# FPGA_Banks_GTH.net
KiCad netlist of a schematic drawn in Altium Designer
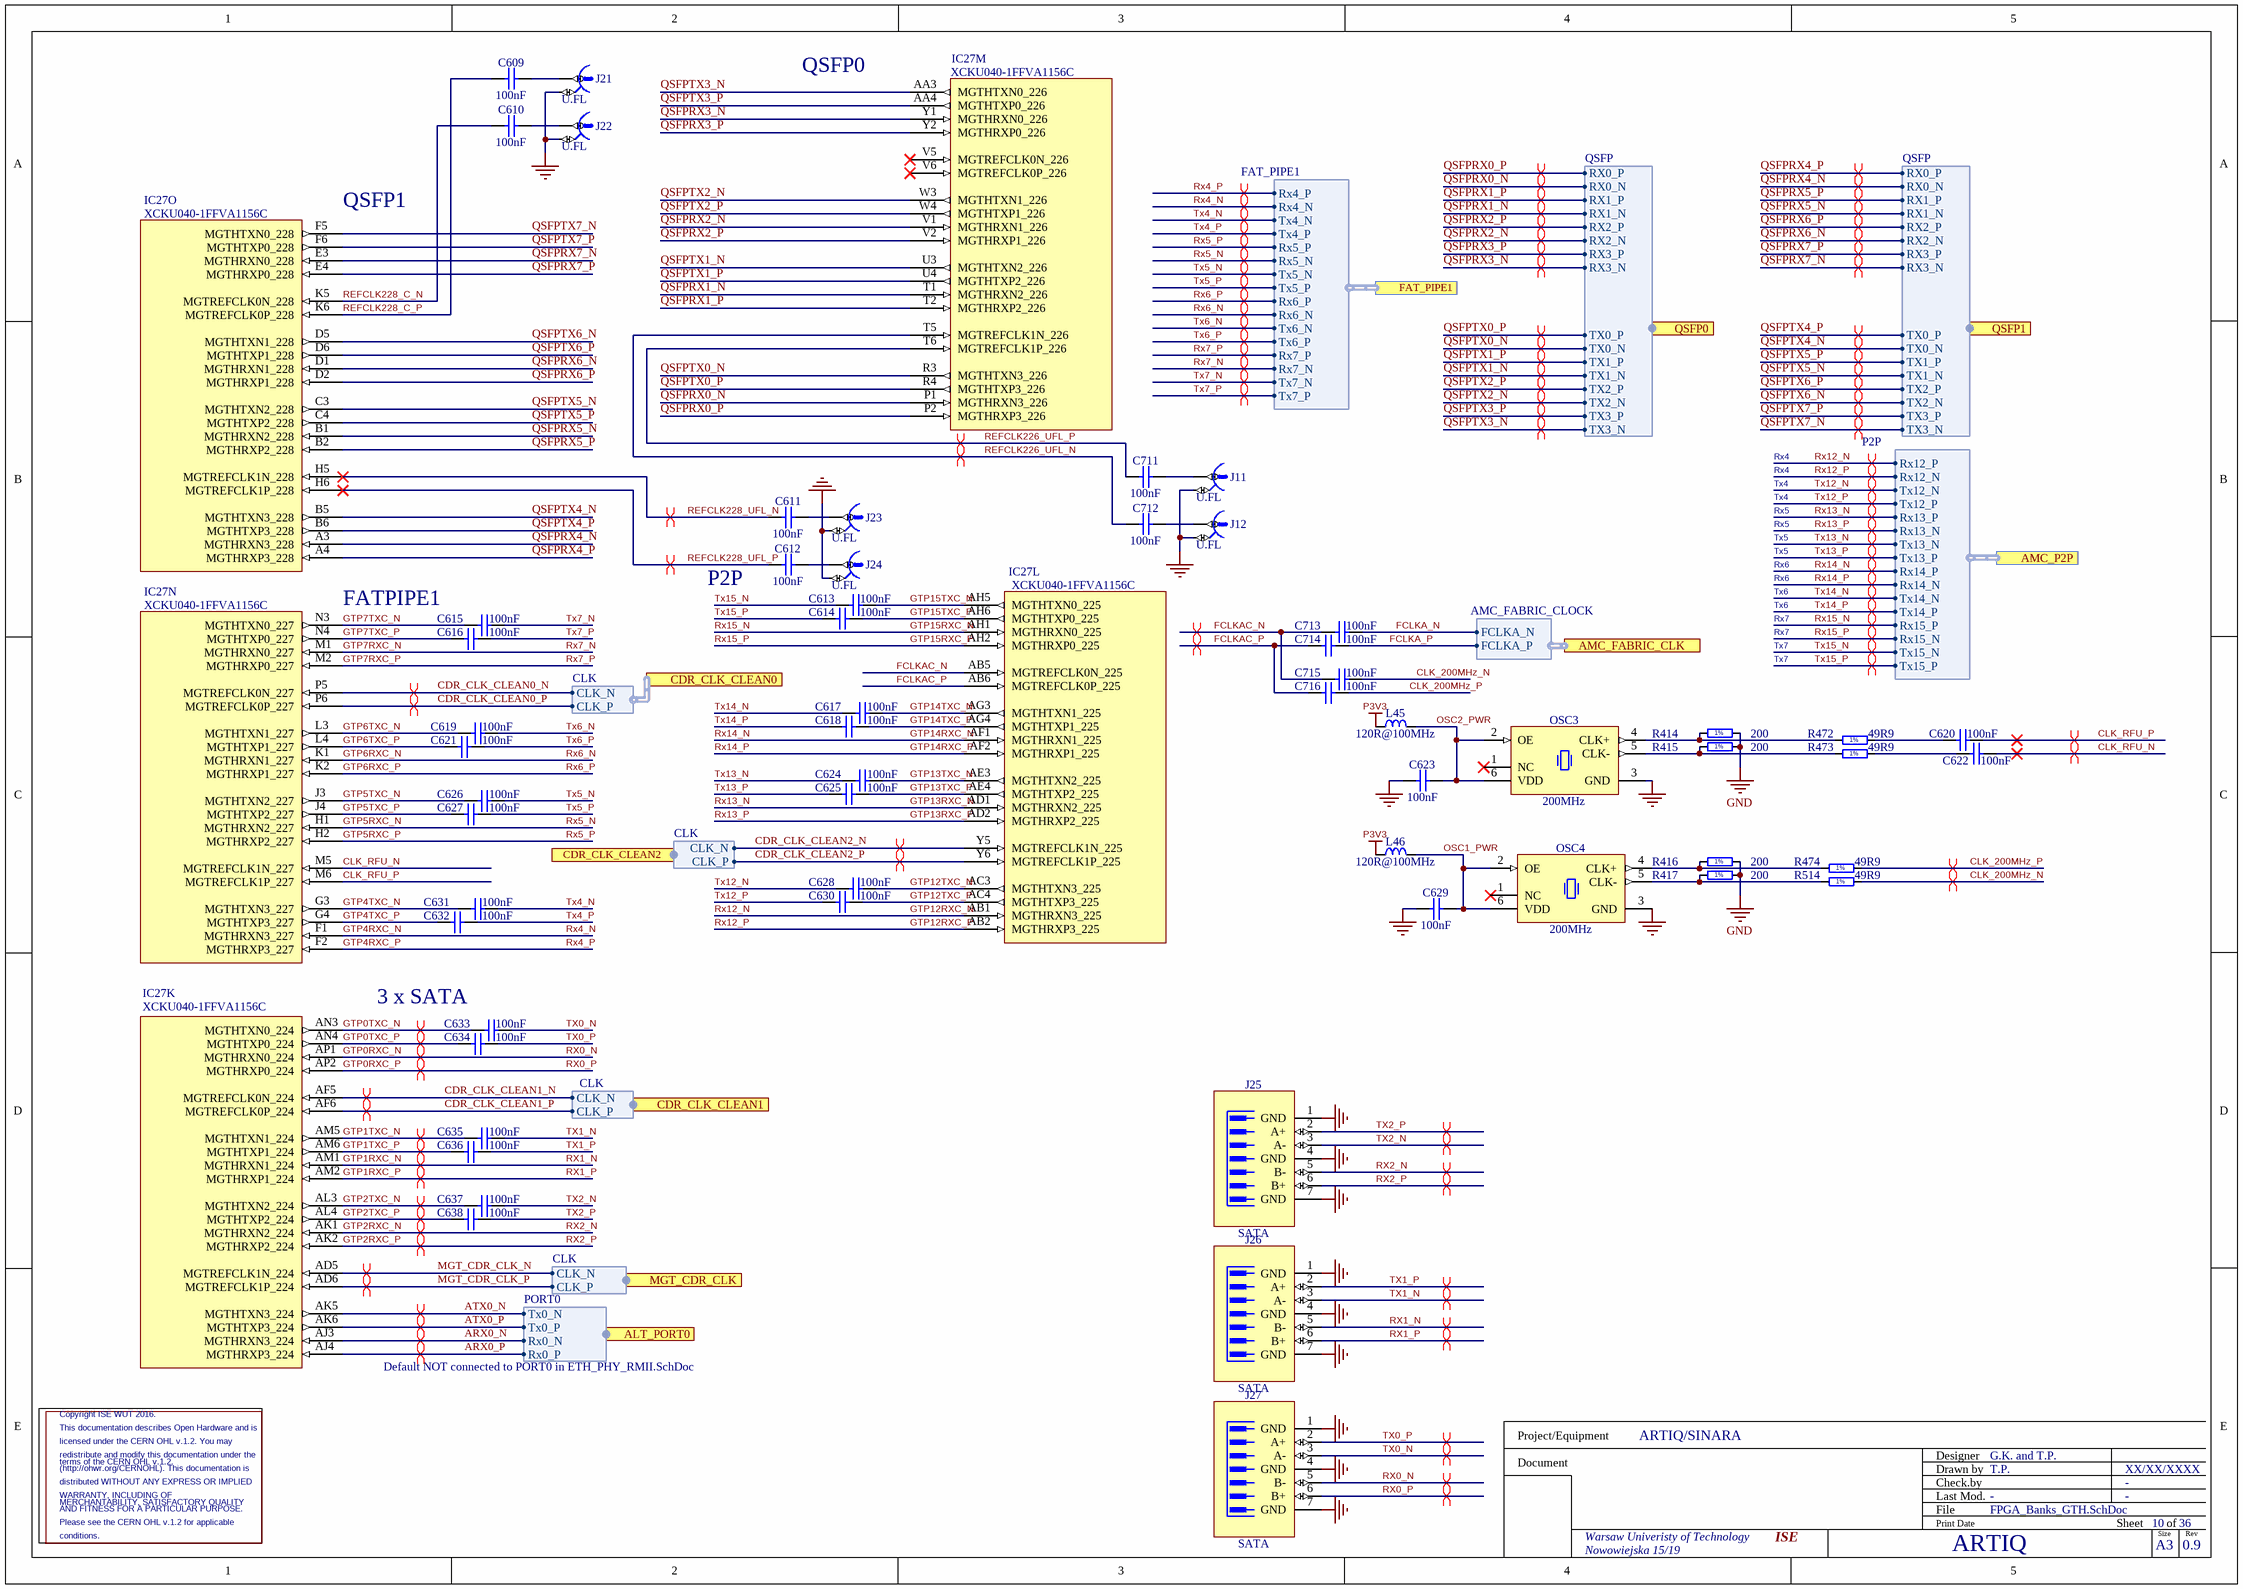
[diagram p0: FPGA_Banks_GTH.SchDoc]

(export (version "E")
  (design (tool "Eeschema 10.0.6"))
  (components
    (comp (ref "C609")
      (value "100nF")
      (footprint "CAPC0603X33N")
      (description "Non-polarised capacitor")
      (fields
        (field (name "MANUFACTURER PART NUMBER") "CC0201_100NF_6.3V_10%_X5R")
        (field (name "MANUFACTURER") "GENERIC")
        (field (name "AUTHOR") "CERN DEM JLC")
      )
      (libsource (lib "Capacitors") (part "Capacitor - non polarized"))
    )
    (comp (ref "C610")
      (value "100nF")
      (footprint "CAPC0603X33N")
      (description "Non-polarised capacitor")
      (fields
        (field (name "MANUFACTURER PART NUMBER") "CC0201_100NF_6.3V_10%_X5R")
        (field (name "MANUFACTURER") "GENERIC")
        (field (name "AUTHOR") "CERN DEM JLC")
      )
      (libsource (lib "Capacitors") (part "Capacitor - non polarized"))
    )
    (comp (ref "C611")
      (value "100nF")
      (footprint "CAPC0603X33N")
      (description "Non-polarised capacitor")
      (fields
        (field (name "MANUFACTURER PART NUMBER") "CC0201_100NF_6.3V_10%_X5R")
        (field (name "MANUFACTURER") "GENERIC")
        (field (name "AUTHOR") "CERN DEM JLC")
      )
      (libsource (lib "Capacitors") (part "Capacitor - non polarized"))
    )
    (comp (ref "C612")
      (value "100nF")
      (footprint "CAPC0603X33N")
      (description "Non-polarised capacitor")
      (fields
        (field (name "MANUFACTURER PART NUMBER") "CC0201_100NF_6.3V_10%_X5R")
        (field (name "MANUFACTURER") "GENERIC")
        (field (name "AUTHOR") "CERN DEM JLC")
      )
      (libsource (lib "Capacitors") (part "Capacitor - non polarized"))
    )
    (comp (ref "C613")
      (value "100nF")
      (footprint "CAPC0603X33N")
      (description "Non-polarised capacitor")
      (fields
        (field (name "MANUFACTURER PART NUMBER") "CC0201_100NF_6.3V_10%_X5R")
        (field (name "MANUFACTURER") "GENERIC")
        (field (name "AUTHOR") "CERN DEM JLC")
      )
      (libsource (lib "Capacitors") (part "Capacitor - non polarized"))
    )
    (comp (ref "C614")
      (value "100nF")
      (footprint "CAPC0603X33N")
      (description "Non-polarised capacitor")
      (fields
        (field (name "MANUFACTURER PART NUMBER") "CC0201_100NF_6.3V_10%_X5R")
        (field (name "MANUFACTURER") "GENERIC")
        (field (name "AUTHOR") "CERN DEM JLC")
      )
      (libsource (lib "Capacitors") (part "Capacitor - non polarized"))
    )
    (comp (ref "C615")
      (value "100nF")
      (footprint "CAPC0603X33N")
      (description "Non-polarised capacitor")
      (fields
        (field (name "MANUFACTURER PART NUMBER") "CC0201_100NF_6.3V_10%_X5R")
        (field (name "MANUFACTURER") "GENERIC")
        (field (name "AUTHOR") "CERN DEM JLC")
      )
      (libsource (lib "Capacitors") (part "Capacitor - non polarized"))
    )
    (comp (ref "C616")
      (value "100nF")
      (footprint "CAPC0603X33N")
      (description "Non-polarised capacitor")
      (fields
        (field (name "MANUFACTURER PART NUMBER") "CC0201_100NF_6.3V_10%_X5R")
        (field (name "MANUFACTURER") "GENERIC")
        (field (name "AUTHOR") "CERN DEM JLC")
      )
      (libsource (lib "Capacitors") (part "Capacitor - non polarized"))
    )
    (comp (ref "C617")
      (value "100nF")
      (footprint "CAPC0603X33N")
      (description "Non-polarised capacitor")
      (fields
        (field (name "MANUFACTURER PART NUMBER") "CC0201_100NF_6.3V_10%_X5R")
        (field (name "MANUFACTURER") "GENERIC")
        (field (name "AUTHOR") "CERN DEM JLC")
      )
      (libsource (lib "Capacitors") (part "Capacitor - non polarized"))
    )
    (comp (ref "C618")
      (value "100nF")
      (footprint "CAPC0603X33N")
      (description "Non-polarised capacitor")
      (fields
        (field (name "MANUFACTURER PART NUMBER") "CC0201_100NF_6.3V_10%_X5R")
        (field (name "MANUFACTURER") "GENERIC")
        (field (name "AUTHOR") "CERN DEM JLC")
      )
      (libsource (lib "Capacitors") (part "Capacitor - non polarized"))
    )
    (comp (ref "C619")
      (value "100nF")
      (footprint "CAPC0603X33N")
      (description "Non-polarised capacitor")
      (fields
        (field (name "MANUFACTURER PART NUMBER") "CC0201_100NF_6.3V_10%_X5R")
        (field (name "MANUFACTURER") "GENERIC")
        (field (name "AUTHOR") "CERN DEM JLC")
      )
      (libsource (lib "Capacitors") (part "Capacitor - non polarized"))
    )
    (comp (ref "C620")
      (value "100nF")
      (footprint "CAPC0603X33N")
      (description "Non-polarised capacitor")
      (fields
        (field (name "MANUFACTURER PART NUMBER") "CC0201_100NF_6.3V_10%_X5R")
        (field (name "MANUFACTURER") "GENERIC")
        (field (name "AUTHOR") "CERN DEM JLC")
      )
      (libsource (lib "Capacitors") (part "Capacitor - non polarized"))
    )
    (comp (ref "C621")
      (value "100nF")
      (footprint "CAPC0603X33N")
      (description "Non-polarised capacitor")
      (fields
        (field (name "MANUFACTURER PART NUMBER") "CC0201_100NF_6.3V_10%_X5R")
        (field (name "MANUFACTURER") "GENERIC")
        (field (name "AUTHOR") "CERN DEM JLC")
      )
      (libsource (lib "Capacitors") (part "Capacitor - non polarized"))
    )
    (comp (ref "C622")
      (value "100nF")
      (footprint "CAPC0603X33N")
      (description "Non-polarised capacitor")
      (fields
        (field (name "MANUFACTURER PART NUMBER") "CC0201_100NF_6.3V_10%_X5R")
        (field (name "MANUFACTURER") "GENERIC")
        (field (name "AUTHOR") "CERN DEM JLC")
      )
      (libsource (lib "Capacitors") (part "Capacitor - non polarized"))
    )
    (comp (ref "C623")
      (value "100nF")
      (footprint "CAPC0603X33N")
      (description "Non-polarised capacitor")
      (fields
        (field (name "MANUFACTURER PART NUMBER") "CC0201_100NF_6.3V_10%_X5R")
        (field (name "MANUFACTURER") "GENERIC")
        (field (name "AUTHOR") "CERN DEM JLC")
      )
      (libsource (lib "Capacitors") (part "Capacitor - non polarized"))
    )
    (comp (ref "C624")
      (value "100nF")
      (footprint "CAPC0603X33N")
      (description "Non-polarised capacitor")
      (fields
        (field (name "MANUFACTURER PART NUMBER") "CC0201_100NF_6.3V_10%_X5R")
        (field (name "MANUFACTURER") "GENERIC")
        (field (name "AUTHOR") "CERN DEM JLC")
      )
      (libsource (lib "Capacitors") (part "Capacitor - non polarized"))
    )
    (comp (ref "C625")
      (value "100nF")
      (footprint "CAPC0603X33N")
      (description "Non-polarised capacitor")
      (fields
        (field (name "MANUFACTURER PART NUMBER") "CC0201_100NF_6.3V_10%_X5R")
        (field (name "MANUFACTURER") "GENERIC")
        (field (name "AUTHOR") "CERN DEM JLC")
      )
      (libsource (lib "Capacitors") (part "Capacitor - non polarized"))
    )
    (comp (ref "C626")
      (value "100nF")
      (footprint "CAPC0603X33N")
      (description "Non-polarised capacitor")
      (fields
        (field (name "MANUFACTURER PART NUMBER") "CC0201_100NF_6.3V_10%_X5R")
        (field (name "MANUFACTURER") "GENERIC")
        (field (name "AUTHOR") "CERN DEM JLC")
      )
      (libsource (lib "Capacitors") (part "Capacitor - non polarized"))
    )
    (comp (ref "C627")
      (value "100nF")
      (footprint "CAPC0603X33N")
      (description "Non-polarised capacitor")
      (fields
        (field (name "MANUFACTURER PART NUMBER") "CC0201_100NF_6.3V_10%_X5R")
        (field (name "MANUFACTURER") "GENERIC")
        (field (name "AUTHOR") "CERN DEM JLC")
      )
      (libsource (lib "Capacitors") (part "Capacitor - non polarized"))
    )
    (comp (ref "C628")
      (value "100nF")
      (footprint "CAPC0603X33N")
      (description "Non-polarised capacitor")
      (fields
        (field (name "MANUFACTURER PART NUMBER") "CC0201_100NF_6.3V_10%_X5R")
        (field (name "MANUFACTURER") "GENERIC")
        (field (name "AUTHOR") "CERN DEM JLC")
      )
      (libsource (lib "Capacitors") (part "Capacitor - non polarized"))
    )
    (comp (ref "C629")
      (value "100nF")
      (footprint "CAPC0603X33N")
      (description "Non-polarised capacitor")
      (fields
        (field (name "MANUFACTURER PART NUMBER") "CC0201_100NF_6.3V_10%_X5R")
        (field (name "MANUFACTURER") "GENERIC")
        (field (name "AUTHOR") "CERN DEM JLC")
      )
      (libsource (lib "Capacitors") (part "Capacitor - non polarized"))
    )
    (comp (ref "C630")
      (value "100nF")
      (footprint "CAPC0603X33N")
      (description "Non-polarised capacitor")
      (fields
        (field (name "MANUFACTURER PART NUMBER") "CC0201_100NF_6.3V_10%_X5R")
        (field (name "MANUFACTURER") "GENERIC")
        (field (name "AUTHOR") "CERN DEM JLC")
      )
      (libsource (lib "Capacitors") (part "Capacitor - non polarized"))
    )
    (comp (ref "C631")
      (value "100nF")
      (footprint "CAPC0603X33N")
      (description "Non-polarised capacitor")
      (fields
        (field (name "MANUFACTURER PART NUMBER") "CC0201_100NF_6.3V_10%_X5R")
        (field (name "MANUFACTURER") "GENERIC")
        (field (name "AUTHOR") "CERN DEM JLC")
      )
      (libsource (lib "Capacitors") (part "Capacitor - non polarized"))
    )
    (comp (ref "C632")
      (value "100nF")
      (footprint "CAPC0603X33N")
      (description "Non-polarised capacitor")
      (fields
        (field (name "MANUFACTURER PART NUMBER") "CC0201_100NF_6.3V_10%_X5R")
        (field (name "MANUFACTURER") "GENERIC")
        (field (name "AUTHOR") "CERN DEM JLC")
      )
      (libsource (lib "Capacitors") (part "Capacitor - non polarized"))
    )
    (comp (ref "C633")
      (value "100nF")
      (footprint "CAPC0603X33N")
      (description "Non-polarised capacitor")
      (fields
        (field (name "MANUFACTURER PART NUMBER") "CC0201_100NF_6.3V_10%_X5R")
        (field (name "MANUFACTURER") "GENERIC")
        (field (name "AUTHOR") "CERN DEM JLC")
      )
      (libsource (lib "Capacitors") (part "Capacitor - non polarized"))
    )
    (comp (ref "C634")
      (value "100nF")
      (footprint "CAPC0603X33N")
      (description "Non-polarised capacitor")
      (fields
        (field (name "MANUFACTURER PART NUMBER") "CC0201_100NF_6.3V_10%_X5R")
        (field (name "MANUFACTURER") "GENERIC")
        (field (name "AUTHOR") "CERN DEM JLC")
      )
      (libsource (lib "Capacitors") (part "Capacitor - non polarized"))
    )
    (comp (ref "C635")
      (value "100nF")
      (footprint "CAPC0603X33N")
      (description "Non-polarised capacitor")
      (fields
        (field (name "MANUFACTURER PART NUMBER") "CC0201_100NF_6.3V_10%_X5R")
        (field (name "MANUFACTURER") "GENERIC")
        (field (name "AUTHOR") "CERN DEM JLC")
      )
      (libsource (lib "Capacitors") (part "Capacitor - non polarized"))
    )
    (comp (ref "C636")
      (value "100nF")
      (footprint "CAPC0603X33N")
      (description "Non-polarised capacitor")
      (fields
        (field (name "MANUFACTURER PART NUMBER") "CC0201_100NF_6.3V_10%_X5R")
        (field (name "MANUFACTURER") "GENERIC")
        (field (name "AUTHOR") "CERN DEM JLC")
      )
      (libsource (lib "Capacitors") (part "Capacitor - non polarized"))
    )
    (comp (ref "C637")
      (value "100nF")
      (footprint "CAPC0603X33N")
      (description "Non-polarised capacitor")
      (fields
        (field (name "MANUFACTURER PART NUMBER") "CC0201_100NF_6.3V_10%_X5R")
        (field (name "MANUFACTURER") "GENERIC")
        (field (name "AUTHOR") "CERN DEM JLC")
      )
      (libsource (lib "Capacitors") (part "Capacitor - non polarized"))
    )
    (comp (ref "C638")
      (value "100nF")
      (footprint "CAPC0603X33N")
      (description "Non-polarised capacitor")
      (fields
        (field (name "MANUFACTURER PART NUMBER") "CC0201_100NF_6.3V_10%_X5R")
        (field (name "MANUFACTURER") "GENERIC")
        (field (name "AUTHOR") "CERN DEM JLC")
      )
      (libsource (lib "Capacitors") (part "Capacitor - non polarized"))
    )
    (comp (ref "C711")
      (value "100nF")
      (footprint "CAPC0603X33N")
      (description "Non-polarised capacitor")
      (fields
        (field (name "MANUFACTURER PART NUMBER") "CC0201_100NF_6.3V_10%_X5R")
        (field (name "MANUFACTURER") "GENERIC")
        (field (name "AUTHOR") "CERN DEM JLC")
      )
      (libsource (lib "Capacitors") (part "Capacitor - non polarized"))
    )
    (comp (ref "C712")
      (value "100nF")
      (footprint "CAPC0603X33N")
      (description "Non-polarised capacitor")
      (fields
        (field (name "MANUFACTURER PART NUMBER") "CC0201_100NF_6.3V_10%_X5R")
        (field (name "MANUFACTURER") "GENERIC")
        (field (name "AUTHOR") "CERN DEM JLC")
      )
      (libsource (lib "Capacitors") (part "Capacitor - non polarized"))
    )
    (comp (ref "C713")
      (value "100nF")
      (footprint "CAPC0603X33N")
      (description "Non-polarised capacitor")
      (fields
        (field (name "MANUFACTURER PART NUMBER") "CC0201_100NF_6.3V_10%_X5R")
        (field (name "MANUFACTURER") "GENERIC")
        (field (name "AUTHOR") "CERN DEM JLC")
      )
      (libsource (lib "Capacitors") (part "Capacitor - non polarized"))
    )
    (comp (ref "C714")
      (value "100nF")
      (footprint "CAPC0603X33N")
      (description "Non-polarised capacitor")
      (fields
        (field (name "MANUFACTURER PART NUMBER") "CC0201_100NF_6.3V_10%_X5R")
        (field (name "MANUFACTURER") "GENERIC")
        (field (name "AUTHOR") "CERN DEM JLC")
      )
      (libsource (lib "Capacitors") (part "Capacitor - non polarized"))
    )
    (comp (ref "C715")
      (value "100nF")
      (footprint "CAPC0603X33N")
      (description "Non-polarised capacitor")
      (fields
        (field (name "MANUFACTURER PART NUMBER") "CC0201_100NF_6.3V_10%_X5R")
        (field (name "MANUFACTURER") "GENERIC")
        (field (name "AUTHOR") "CERN DEM JLC")
      )
      (libsource (lib "Capacitors") (part "Capacitor - non polarized"))
    )
    (comp (ref "C716")
      (value "100nF")
      (footprint "CAPC0603X33N")
      (description "Non-polarised capacitor")
      (fields
        (field (name "MANUFACTURER PART NUMBER") "CC0201_100NF_6.3V_10%_X5R")
        (field (name "MANUFACTURER") "GENERIC")
        (field (name "AUTHOR") "CERN DEM JLC")
      )
      (libsource (lib "Capacitors") (part "Capacitor - non polarized"))
    )
    (comp (ref "IC27")
      (value "XCKU040-1FFVA1156C")
      (footprint "BGA1156C100P34X34_3500X3500X350")
      (description "Kintex UltraScale FPGA, 520 I/O, 530K Cells, 1156-Ball BGA, Speed Grade 1, Commercial Grade")
      (fields (field (name "MANUFACTURER") "XILINX") (field (name "AUTHOR") "CERN DEM CA"))
      (libsource (lib "") (part "XCKU040-1FFVA1156C_1"))
    )
    (comp (ref "J11")
      (value "U.FL")
      (footprint "HIROSE_U.FL-R-SMT-1(10)")
      (fields
        (field (name "MANUFACTURER PART NUMBER") "U.FL-R-SMT-1(10)")
        (field (name "MANUFACTURER") "HIROSE (HRS)")
        (field (name "PART NUMBER") "HIROSE_U.FL-R-SMT-1(10)")
        (field (name "AUTHOR") "CERN DEM JLC")
      )
      (libsource (lib "Connectors") (part "Coax_1Male_1Shield"))
    )
    (comp (ref "J12")
      (value "U.FL")
      (footprint "HIROSE_U.FL-R-SMT-1(10)")
      (fields
        (field (name "MANUFACTURER PART NUMBER") "U.FL-R-SMT-1(10)")
        (field (name "MANUFACTURER") "HIROSE (HRS)")
        (field (name "PART NUMBER") "HIROSE_U.FL-R-SMT-1(10)")
        (field (name "AUTHOR") "CERN DEM JLC")
      )
      (libsource (lib "Connectors") (part "Coax_1Male_1Shield"))
    )
    (comp (ref "J21")
      (value "U.FL")
      (footprint "HIROSE_U.FL-R-SMT-1(10)")
      (fields
        (field (name "MANUFACTURER PART NUMBER") "U.FL-R-SMT-1(10)")
        (field (name "MANUFACTURER") "HIROSE (HRS)")
        (field (name "PART NUMBER") "HIROSE_U.FL-R-SMT-1(10)")
        (field (name "AUTHOR") "CERN DEM JLC")
      )
      (libsource (lib "Connectors") (part "Coax_1Male_1Shield"))
    )
    (comp (ref "J22")
      (value "U.FL")
      (footprint "HIROSE_U.FL-R-SMT-1(10)")
      (fields
        (field (name "MANUFACTURER PART NUMBER") "U.FL-R-SMT-1(10)")
        (field (name "MANUFACTURER") "HIROSE (HRS)")
        (field (name "PART NUMBER") "HIROSE_U.FL-R-SMT-1(10)")
        (field (name "AUTHOR") "CERN DEM JLC")
      )
      (libsource (lib "Connectors") (part "Coax_1Male_1Shield"))
    )
    (comp (ref "J23")
      (value "U.FL")
      (footprint "HIROSE_U.FL-R-SMT-1(10)")
      (fields
        (field (name "MANUFACTURER PART NUMBER") "U.FL-R-SMT-1(10)")
        (field (name "MANUFACTURER") "HIROSE (HRS)")
        (field (name "PART NUMBER") "HIROSE_U.FL-R-SMT-1(10)")
        (field (name "AUTHOR") "CERN DEM JLC")
      )
      (libsource (lib "Connectors") (part "Coax_1Male_1Shield"))
    )
    (comp (ref "J24")
      (value "U.FL")
      (footprint "HIROSE_U.FL-R-SMT-1(10)")
      (fields
        (field (name "MANUFACTURER PART NUMBER") "U.FL-R-SMT-1(10)")
        (field (name "MANUFACTURER") "HIROSE (HRS)")
        (field (name "PART NUMBER") "HIROSE_U.FL-R-SMT-1(10)")
        (field (name "AUTHOR") "CERN DEM JLC")
      )
      (libsource (lib "Connectors") (part "Coax_1Male_1Shield"))
    )
    (comp (ref "J25")
      (value "SATA")
      (footprint "MOLEX_67800-5005")
      (description "7 Pin SATA Receptacle")
      (fields
        (field (name "MANUFACTURER PART NUMBER") "67800-5005")
        (field (name "MANUFACTURER") "MOLEX")
        (field (name "AUTHOR") "CERN DEM MR")
      )
      (libsource (lib "Connectors") (part "Connector SATA 7 Male"))
    )
    (comp (ref "J26")
      (value "SATA")
      (footprint "MOLEX_67800-5005")
      (description "7 Pin SATA Receptacle")
      (fields
        (field (name "MANUFACTURER PART NUMBER") "67800-5005")
        (field (name "MANUFACTURER") "MOLEX")
        (field (name "AUTHOR") "CERN DEM MR")
      )
      (libsource (lib "Connectors") (part "Connector SATA 7 Male"))
    )
    (comp (ref "J27")
      (value "SATA")
      (footprint "MOLEX_67800-5005")
      (description "7 Pin SATA Receptacle")
      (fields
        (field (name "MANUFACTURER PART NUMBER") "67800-5005")
        (field (name "MANUFACTURER") "MOLEX")
        (field (name "AUTHOR") "CERN DEM MR")
      )
      (libsource (lib "Connectors") (part "Connector SATA 7 Male"))
    )
    (comp (ref "L45")
      (value "120R@100MHz")
      (footprint "INDC1005X55N")
      (description "Inductor")
      (fields
        (field (name "MANUFACTURER PART NUMBER") "BLM15PX121SN1D")
        (field (name "MANUFACTURER") "MURATA")
        (field (name "AUTHOR") "CERN DEM JMW")
      )
      (libsource (lib "Inductors & Transformers") (part "Inductor"))
    )
    (comp (ref "L46")
      (value "120R@100MHz")
      (footprint "INDC1005X55N")
      (description "Inductor")
      (fields
        (field (name "MANUFACTURER PART NUMBER") "BLM15PX121SN1D")
        (field (name "MANUFACTURER") "MURATA")
        (field (name "AUTHOR") "CERN DEM JMW")
      )
      (libsource (lib "Inductors & Transformers") (part "Inductor"))
    )
    (comp (ref "OSC3")
      (value "200MHz")
      (footprint "OSC_SILICON-LAB_SI510-6N(5X7)")
      (description "Crystal Oscillator 6 pins, Si510 (LVDS/LVPECL/HCSL/Dual CMOS)")
      (fields
        (field (name "MANUFACTURER PART NUMBER") "510ABA200M000AAG")
        (field (name "PART NUMBER") "OSC_200MHZ_SILICON-LAB_510ABA200M000AAG")
      )
      (libsource (lib "TP_LIB") (part "OSC_200MHZ_SILICON-LAB_510ABA200M000AAG"))
    )
    (comp (ref "OSC4")
      (value "200MHz")
      (footprint "OSC_SILICON-LAB_SI510-6N(5X7)")
      (description "Crystal Oscillator 6 pins, Si510 (LVDS/LVPECL/HCSL/Dual CMOS)")
      (fields
        (field (name "MANUFACTURER PART NUMBER") "510ABA200M000AAG")
        (field (name "PART NUMBER") "OSC_200MHZ_SILICON-LAB_510ABA200M000AAG")
      )
      (libsource (lib "TP_LIB") (part "OSC_200MHZ_SILICON-LAB_510ABA200M000AAG"))
    )
    (comp (ref "R414")
      (value "200")
      (footprint "RESC1005X40N")
      (description "Resistor - 1%")
      (fields
        (field (name "MANUFACTURER PART NUMBER") "R0402_200R_1%_0.0625W_100PPM")
        (field (name "MANUFACTURER") "GENERIC")
        (field (name "AUTHOR") "CERN DEM JLC")
      )
      (libsource (lib "Resistors") (part "Resistor - 1%"))
    )
    (comp (ref "R415")
      (value "200")
      (footprint "RESC1005X40N")
      (description "Resistor - 1%")
      (fields
        (field (name "MANUFACTURER PART NUMBER") "R0402_200R_1%_0.0625W_100PPM")
        (field (name "MANUFACTURER") "GENERIC")
        (field (name "AUTHOR") "CERN DEM JLC")
      )
      (libsource (lib "Resistors") (part "Resistor - 1%"))
    )
    (comp (ref "R416")
      (value "200")
      (footprint "RESC1005X40N")
      (description "Resistor - 1%")
      (fields
        (field (name "MANUFACTURER PART NUMBER") "R0402_200R_1%_0.0625W_100PPM")
        (field (name "MANUFACTURER") "GENERIC")
        (field (name "AUTHOR") "CERN DEM JLC")
      )
      (libsource (lib "Resistors") (part "Resistor - 1%"))
    )
    (comp (ref "R417")
      (value "200")
      (footprint "RESC1005X40N")
      (description "Resistor - 1%")
      (fields
        (field (name "MANUFACTURER PART NUMBER") "R0402_200R_1%_0.0625W_100PPM")
        (field (name "MANUFACTURER") "GENERIC")
        (field (name "AUTHOR") "CERN DEM JLC")
      )
      (libsource (lib "Resistors") (part "Resistor - 1%"))
    )
    (comp (ref "R472")
      (value "49R9")
      (footprint "RESC1005X40N")
      (description "Resistor - 1%")
      (fields
        (field (name "MANUFACTURER PART NUMBER") "R0402_49R9_1%_0.0625W_100PPM")
        (field (name "MANUFACTURER") "GENERIC")
        (field (name "AUTHOR") "CERN DEM JLC")
      )
      (libsource (lib "Resistors") (part "Resistor - 1%"))
    )
    (comp (ref "R473")
      (value "49R9")
      (footprint "RESC1005X40N")
      (description "Resistor - 1%")
      (fields
        (field (name "MANUFACTURER PART NUMBER") "R0402_49R9_1%_0.0625W_100PPM")
        (field (name "MANUFACTURER") "GENERIC")
        (field (name "AUTHOR") "CERN DEM JLC")
      )
      (libsource (lib "Resistors") (part "Resistor - 1%"))
    )
    (comp (ref "R474")
      (value "49R9")
      (footprint "RESC1005X40N")
      (description "Resistor - 1%")
      (fields
        (field (name "MANUFACTURER PART NUMBER") "R0402_49R9_1%_0.0625W_100PPM")
        (field (name "MANUFACTURER") "GENERIC")
        (field (name "AUTHOR") "CERN DEM JLC")
      )
      (libsource (lib "Resistors") (part "Resistor - 1%"))
    )
    (comp (ref "R514")
      (value "49R9")
      (footprint "RESC1005X40N")
      (description "Resistor - 1%")
      (fields
        (field (name "MANUFACTURER PART NUMBER") "R0402_49R9_1%_0.0625W_100PPM")
        (field (name "MANUFACTURER") "GENERIC")
        (field (name "AUTHOR") "CERN DEM JLC")
      )
      (libsource (lib "Resistors") (part "Resistor - 1%"))
    )
  )
  (nets
    (net (code "7") (name "/ARX0_N") (class "Default")
      (node (ref "IC27") (pin "AJ3") (pinfunction "MGTHRXN3_224_AJ3") (pintype "input"))
    )
    (net (code "8") (name "/ARX0_P") (class "Default")
      (node (ref "IC27") (pin "AJ4") (pinfunction "MGTHRXP3_224_AJ4") (pintype "input"))
    )
    (net (code "9") (name "/ATX0_N") (class "Default")
      (node (ref "IC27") (pin "AK5") (pinfunction "MGTHTXN3_224_AK5") (pintype "output"))
    )
    (net (code "10") (name "/ATX0_P") (class "Default")
      (node (ref "IC27") (pin "AK6") (pinfunction "MGTHTXP3_224_AK6") (pintype "output"))
    )
    (net (code "11") (name "/CDR_CLK_CLEAN0_N") (class "Default")
      (node (ref "IC27") (pin "P5") (pinfunction "MGTREFCLK0N_227_P5") (pintype "input"))
    )
    (net (code "12") (name "/CDR_CLK_CLEAN0_P") (class "Default")
      (node (ref "IC27") (pin "P6") (pinfunction "MGTREFCLK0P_227_P6") (pintype "input"))
    )
    (net (code "13") (name "/CDR_CLK_CLEAN1_N") (class "Default")
      (node (ref "IC27") (pin "AF5") (pinfunction "MGTREFCLK0N_224_AF5") (pintype "input"))
    )
    (net (code "14") (name "/CDR_CLK_CLEAN1_P") (class "Default")
      (node (ref "IC27") (pin "AF6") (pinfunction "MGTREFCLK0P_224_AF6") (pintype "input"))
    )
    (net (code "15") (name "/CDR_CLK_CLEAN2_N") (class "Default")
      (node (ref "IC27") (pin "Y5") (pinfunction "MGTREFCLK1N_225_Y5") (pintype "input"))
    )
    (net (code "16") (name "/CDR_CLK_CLEAN2_P") (class "Default")
      (node (ref "IC27") (pin "Y6") (pinfunction "MGTREFCLK1P_225_Y6") (pintype "input"))
    )
    (net (code "17") (name "/CLK_200MHz_N") (class "Default")
      (node (ref "C715") (pin "2") (pinfunction "2_2") (pintype "passive"))
      (node (ref "R514") (pin "2") (pinfunction "2_2") (pintype "passive"))
    )
    (net (code "18") (name "/CLK_200MHz_P") (class "Default")
      (node (ref "C716") (pin "2") (pinfunction "2_2") (pintype "passive"))
      (node (ref "R474") (pin "2") (pinfunction "2_2") (pintype "passive"))
    )
    (net (code "19") (name "/CLK_RFU_N") (class "Default")
      (node (ref "C622") (pin "2") (pinfunction "2_2") (pintype "passive"))
      (node (ref "IC27") (pin "M5") (pinfunction "MGTREFCLK1N_227_M5") (pintype "input"))
    )
    (net (code "20") (name "/CLK_RFU_P") (class "Default")
      (node (ref "C620") (pin "2") (pinfunction "2_2") (pintype "passive"))
      (node (ref "IC27") (pin "M6") (pinfunction "MGTREFCLK1P_227_M6") (pintype "input"))
    )
    (net (code "21") (name "/FCLKAC_N") (class "Default")
      (node (ref "C713") (pin "1") (pinfunction "1_1") (pintype "passive"))
      (node (ref "C715") (pin "1") (pinfunction "1_1") (pintype "passive"))
      (node (ref "IC27") (pin "AB5") (pinfunction "MGTREFCLK0N_225_AB5") (pintype "input"))
    )
    (net (code "22") (name "/FCLKAC_P") (class "Default")
      (node (ref "C714") (pin "1") (pinfunction "1_1") (pintype "passive"))
      (node (ref "C716") (pin "1") (pinfunction "1_1") (pintype "passive"))
      (node (ref "IC27") (pin "AB6") (pinfunction "MGTREFCLK0P_225_AB6") (pintype "input"))
    )
    (net (code "23") (name "/FCLKA_N") (class "Default")
      (node (ref "C713") (pin "2") (pinfunction "2_2") (pintype "passive"))
    )
    (net (code "24") (name "/FCLKA_P") (class "Default")
      (node (ref "C714") (pin "2") (pinfunction "2_2") (pintype "passive"))
    )
    (net (code "25") (name "/GTP0RXC_N") (class "Default")
      (node (ref "IC27") (pin "AP1") (pinfunction "MGTHRXN0_224_AP1") (pintype "input"))
      (node (ref "J27") (pin "5") (pinfunction "B-_5") (pintype "bidirectional"))
    )
    (net (code "26") (name "/GTP0RXC_P") (class "Default")
      (node (ref "IC27") (pin "AP2") (pinfunction "MGTHRXP0_224_AP2") (pintype "input"))
      (node (ref "J27") (pin "6") (pinfunction "B+_6") (pintype "bidirectional"))
    )
    (net (code "27") (name "/GTP0TXC_N") (class "Default")
      (node (ref "C633") (pin "1") (pinfunction "1_1") (pintype "passive"))
      (node (ref "IC27") (pin "AN3") (pinfunction "MGTHTXN0_224_AN3") (pintype "output"))
    )
    (net (code "28") (name "/GTP0TXC_P") (class "Default")
      (node (ref "C634") (pin "1") (pinfunction "1_1") (pintype "passive"))
      (node (ref "IC27") (pin "AN4") (pinfunction "MGTHTXP0_224_AN4") (pintype "output"))
    )
    (net (code "29") (name "/GTP1RXC_N") (class "Default")
      (node (ref "IC27") (pin "AM1") (pinfunction "MGTHRXN1_224_AM1") (pintype "input"))
      (node (ref "J26") (pin "5") (pinfunction "B-_5") (pintype "bidirectional"))
    )
    (net (code "30") (name "/GTP1RXC_P") (class "Default")
      (node (ref "IC27") (pin "AM2") (pinfunction "MGTHRXP1_224_AM2") (pintype "input"))
      (node (ref "J26") (pin "6") (pinfunction "B+_6") (pintype "bidirectional"))
    )
    (net (code "31") (name "/GTP1TXC_N") (class "Default")
      (node (ref "C635") (pin "1") (pinfunction "1_1") (pintype "passive"))
      (node (ref "IC27") (pin "AM5") (pinfunction "MGTHTXN1_224_AM5") (pintype "output"))
    )
    (net (code "32") (name "/GTP1TXC_P") (class "Default")
      (node (ref "C636") (pin "1") (pinfunction "1_1") (pintype "passive"))
      (node (ref "IC27") (pin "AM6") (pinfunction "MGTHTXP1_224_AM6") (pintype "output"))
    )
    (net (code "33") (name "/GTP2RXC_N") (class "Default")
      (node (ref "IC27") (pin "AK1") (pinfunction "MGTHRXN2_224_AK1") (pintype "input"))
      (node (ref "J25") (pin "5") (pinfunction "B-_5") (pintype "bidirectional"))
    )
    (net (code "34") (name "/GTP2RXC_P") (class "Default")
      (node (ref "IC27") (pin "AK2") (pinfunction "MGTHRXP2_224_AK2") (pintype "input"))
      (node (ref "J25") (pin "6") (pinfunction "B+_6") (pintype "bidirectional"))
    )
    (net (code "35") (name "/GTP2TXC_N") (class "Default")
      (node (ref "C637") (pin "1") (pinfunction "1_1") (pintype "passive"))
      (node (ref "IC27") (pin "AL3") (pinfunction "MGTHTXN2_224_AL3") (pintype "output"))
    )
    (net (code "36") (name "/GTP2TXC_P") (class "Default")
      (node (ref "C638") (pin "1") (pinfunction "1_1") (pintype "passive"))
      (node (ref "IC27") (pin "AL4") (pinfunction "MGTHTXP2_224_AL4") (pintype "output"))
    )
    (net (code "37") (name "/GTP4RXC_N") (class "Default")
      (node (ref "IC27") (pin "F1") (pinfunction "MGTHRXN3_227_F1") (pintype "input"))
    )
    (net (code "38") (name "/GTP4RXC_P") (class "Default")
      (node (ref "IC27") (pin "F2") (pinfunction "MGTHRXP3_227_F2") (pintype "input"))
    )
    (net (code "39") (name "/GTP4TXC_N") (class "Default")
      (node (ref "C631") (pin "1") (pinfunction "1_1") (pintype "passive"))
      (node (ref "IC27") (pin "G3") (pinfunction "MGTHTXN3_227_G3") (pintype "output"))
    )
    (net (code "40") (name "/GTP4TXC_P") (class "Default")
      (node (ref "C632") (pin "1") (pinfunction "1_1") (pintype "passive"))
      (node (ref "IC27") (pin "G4") (pinfunction "MGTHTXP3_227_G4") (pintype "output"))
    )
    (net (code "41") (name "/GTP5RXC_N") (class "Default")
      (node (ref "IC27") (pin "H1") (pinfunction "MGTHRXN2_227_H1") (pintype "input"))
    )
    (net (code "42") (name "/GTP5RXC_P") (class "Default")
      (node (ref "IC27") (pin "H2") (pinfunction "MGTHRXP2_227_H2") (pintype "input"))
    )
    (net (code "43") (name "/GTP5TXC_N") (class "Default")
      (node (ref "C626") (pin "1") (pinfunction "1_1") (pintype "passive"))
      (node (ref "IC27") (pin "J3") (pinfunction "MGTHTXN2_227_J3") (pintype "output"))
    )
    (net (code "44") (name "/GTP5TXC_P") (class "Default")
      (node (ref "C627") (pin "1") (pinfunction "1_1") (pintype "passive"))
      (node (ref "IC27") (pin "J4") (pinfunction "MGTHTXP2_227_J4") (pintype "output"))
    )
    (net (code "45") (name "/GTP6RXC_N") (class "Default")
      (node (ref "IC27") (pin "K1") (pinfunction "MGTHRXN1_227_K1") (pintype "input"))
    )
    (net (code "46") (name "/GTP6RXC_P") (class "Default")
      (node (ref "IC27") (pin "K2") (pinfunction "MGTHRXP1_227_K2") (pintype "input"))
    )
    (net (code "47") (name "/GTP6TXC_N") (class "Default")
      (node (ref "C619") (pin "1") (pinfunction "1_1") (pintype "passive"))
      (node (ref "IC27") (pin "L3") (pinfunction "MGTHTXN1_227_L3") (pintype "output"))
    )
    (net (code "48") (name "/GTP6TXC_P") (class "Default")
      (node (ref "C621") (pin "1") (pinfunction "1_1") (pintype "passive"))
      (node (ref "IC27") (pin "L4") (pinfunction "MGTHTXP1_227_L4") (pintype "output"))
    )
    (net (code "49") (name "/GTP7RXC_N") (class "Default")
      (node (ref "IC27") (pin "M1") (pinfunction "MGTHRXN0_227_M1") (pintype "input"))
    )
    (net (code "50") (name "/GTP7RXC_P") (class "Default")
      (node (ref "IC27") (pin "M2") (pinfunction "MGTHRXP0_227_M2") (pintype "input"))
    )
    (net (code "51") (name "/GTP7TXC_N") (class "Default")
      (node (ref "C615") (pin "1") (pinfunction "1_1") (pintype "passive"))
      (node (ref "IC27") (pin "N3") (pinfunction "MGTHTXN0_227_N3") (pintype "output"))
    )
    (net (code "52") (name "/GTP7TXC_P") (class "Default")
      (node (ref "C616") (pin "1") (pinfunction "1_1") (pintype "passive"))
      (node (ref "IC27") (pin "N4") (pinfunction "MGTHTXP0_227_N4") (pintype "output"))
    )
    (net (code "53") (name "/GTP12RXC_N") (class "Default")
      (node (ref "IC27") (pin "AB1") (pinfunction "MGTHRXN3_225_AB1") (pintype "input"))
    )
    (net (code "54") (name "/GTP12RXC_P") (class "Default")
      (node (ref "IC27") (pin "AB2") (pinfunction "MGTHRXP3_225_AB2") (pintype "input"))
    )
    (net (code "55") (name "/GTP12TXC_N") (class "Default")
      (node (ref "C628") (pin "2") (pinfunction "2_2") (pintype "passive"))
      (node (ref "IC27") (pin "AC3") (pinfunction "MGTHTXN3_225_AC3") (pintype "output"))
    )
    (net (code "56") (name "/GTP12TXC_P") (class "Default")
      (node (ref "C630") (pin "2") (pinfunction "2_2") (pintype "passive"))
      (node (ref "IC27") (pin "AC4") (pinfunction "MGTHTXP3_225_AC4") (pintype "output"))
    )
    (net (code "57") (name "/GTP13RXC_N") (class "Default")
      (node (ref "IC27") (pin "AD1") (pinfunction "MGTHRXN2_225_AD1") (pintype "input"))
    )
    (net (code "58") (name "/GTP13RXC_P") (class "Default")
      (node (ref "IC27") (pin "AD2") (pinfunction "MGTHRXP2_225_AD2") (pintype "input"))
    )
    (net (code "59") (name "/GTP13TXC_N") (class "Default")
      (node (ref "C624") (pin "2") (pinfunction "2_2") (pintype "passive"))
      (node (ref "IC27") (pin "AE3") (pinfunction "MGTHTXN2_225_AE3") (pintype "output"))
    )
    (net (code "60") (name "/GTP13TXC_P") (class "Default")
      (node (ref "C625") (pin "2") (pinfunction "2_2") (pintype "passive"))
      (node (ref "IC27") (pin "AE4") (pinfunction "MGTHTXP2_225_AE4") (pintype "output"))
    )
    (net (code "61") (name "/GTP14RXC_N") (class "Default")
      (node (ref "IC27") (pin "AF1") (pinfunction "MGTHRXN1_225_AF1") (pintype "input"))
    )
    (net (code "62") (name "/GTP14RXC_P") (class "Default")
      (node (ref "IC27") (pin "AF2") (pinfunction "MGTHRXP1_225_AF2") (pintype "input"))
    )
    (net (code "63") (name "/GTP14TXC_N") (class "Default")
      (node (ref "C617") (pin "2") (pinfunction "2_2") (pintype "passive"))
      (node (ref "IC27") (pin "AG3") (pinfunction "MGTHTXN1_225_AG3") (pintype "output"))
    )
    (net (code "64") (name "/GTP14TXC_P") (class "Default")
      (node (ref "C618") (pin "2") (pinfunction "2_2") (pintype "passive"))
      (node (ref "IC27") (pin "AG4") (pinfunction "MGTHTXP1_225_AG4") (pintype "output"))
    )
    (net (code "65") (name "/GTP15RXC_N") (class "Default")
      (node (ref "IC27") (pin "AH1") (pinfunction "MGTHRXN0_225_AH1") (pintype "input"))
    )
    (net (code "66") (name "/GTP15RXC_P") (class "Default")
      (node (ref "IC27") (pin "AH2") (pinfunction "MGTHRXP0_225_AH2") (pintype "input"))
    )
    (net (code "67") (name "/GTP15TXC_N") (class "Default")
      (node (ref "C613") (pin "2") (pinfunction "2_2") (pintype "passive"))
      (node (ref "IC27") (pin "AH5") (pinfunction "MGTHTXN0_225_AH5") (pintype "output"))
    )
    (net (code "68") (name "/GTP15TXC_P") (class "Default")
      (node (ref "C614") (pin "2") (pinfunction "2_2") (pintype "passive"))
      (node (ref "IC27") (pin "AH6") (pinfunction "MGTHTXP0_225_AH6") (pintype "output"))
    )
    (net (code "69") (name "/MGT_CDR_CLK_N") (class "Default")
      (node (ref "IC27") (pin "AD5") (pinfunction "MGTREFCLK1N_224_AD5") (pintype "input"))
    )
    (net (code "70") (name "/MGT_CDR_CLK_P") (class "Default")
      (node (ref "IC27") (pin "AD6") (pinfunction "MGTREFCLK1P_224_AD6") (pintype "input"))
    )
    (net (code "71") (name "/OSC1_PWR") (class "Default")
      (node (ref "C629") (pin "2") (pinfunction "2_2") (pintype "passive"))
      (node (ref "L46") (pin "1") (pinfunction "1_1") (pintype "passive"))
      (node (ref "OSC4") (pin "2") (pinfunction "OE_2") (pintype "input"))
      (node (ref "OSC4") (pin "6") (pinfunction "VDD_6") (pintype "power_in"))
    )
    (net (code "72") (name "/OSC2_PWR") (class "Default")
      (node (ref "C623") (pin "2") (pinfunction "2_2") (pintype "passive"))
      (node (ref "L45") (pin "1") (pinfunction "1_1") (pintype "passive"))
      (node (ref "OSC3") (pin "2") (pinfunction "OE_2") (pintype "input"))
      (node (ref "OSC3") (pin "6") (pinfunction "VDD_6") (pintype "power_in"))
    )
    (net (code "73") (name "/QSFPRX0_N") (class "Default")
      (node (ref "IC27") (pin "P1") (pinfunction "MGTHRXN3_226_P1") (pintype "input"))
    )
    (net (code "74") (name "/QSFPRX0_P") (class "Default")
      (node (ref "IC27") (pin "P2") (pinfunction "MGTHRXP3_226_P2") (pintype "input"))
    )
    (net (code "75") (name "/QSFPRX1_N") (class "Default")
      (node (ref "IC27") (pin "T1") (pinfunction "MGTHRXN2_226_T1") (pintype "input"))
    )
    (net (code "76") (name "/QSFPRX1_P") (class "Default")
      (node (ref "IC27") (pin "T2") (pinfunction "MGTHRXP2_226_T2") (pintype "input"))
    )
    (net (code "77") (name "/QSFPRX2_N") (class "Default")
      (node (ref "IC27") (pin "V1") (pinfunction "MGTHRXN1_226_V1") (pintype "input"))
    )
    (net (code "78") (name "/QSFPRX2_P") (class "Default")
      (node (ref "IC27") (pin "V2") (pinfunction "MGTHRXP1_226_V2") (pintype "input"))
    )
    (net (code "79") (name "/QSFPRX3_N") (class "Default")
      (node (ref "IC27") (pin "Y1") (pinfunction "MGTHRXN0_226_Y1") (pintype "input"))
    )
    (net (code "80") (name "/QSFPRX3_P") (class "Default")
      (node (ref "IC27") (pin "Y2") (pinfunction "MGTHRXP0_226_Y2") (pintype "input"))
    )
    (net (code "81") (name "/QSFPRX4_N") (class "Default")
      (node (ref "IC27") (pin "A3") (pinfunction "MGTHRXN3_228_A3") (pintype "input"))
    )
    (net (code "82") (name "/QSFPRX4_P") (class "Default")
      (node (ref "IC27") (pin "A4") (pinfunction "MGTHRXP3_228_A4") (pintype "input"))
    )
    (net (code "83") (name "/QSFPRX5_N") (class "Default")
      (node (ref "IC27") (pin "B1") (pinfunction "MGTHRXN2_228_B1") (pintype "input"))
    )
    (net (code "84") (name "/QSFPRX5_P") (class "Default")
      (node (ref "IC27") (pin "B2") (pinfunction "MGTHRXP2_228_B2") (pintype "input"))
    )
    (net (code "85") (name "/QSFPRX6_N") (class "Default")
      (node (ref "IC27") (pin "D1") (pinfunction "MGTHRXN1_228_D1") (pintype "input"))
    )
    (net (code "86") (name "/QSFPRX6_P") (class "Default")
      (node (ref "IC27") (pin "D2") (pinfunction "MGTHRXP1_228_D2") (pintype "input"))
    )
    (net (code "87") (name "/QSFPRX7_N") (class "Default")
      (node (ref "IC27") (pin "E3") (pinfunction "MGTHRXN0_228_E3") (pintype "input"))
    )
    (net (code "88") (name "/QSFPRX7_P") (class "Default")
      (node (ref "IC27") (pin "E4") (pinfunction "MGTHRXP0_228_E4") (pintype "input"))
    )
    (net (code "89") (name "/QSFPTX0_N") (class "Default")
      (node (ref "IC27") (pin "R3") (pinfunction "MGTHTXN3_226_R3") (pintype "output"))
    )
    (net (code "90") (name "/QSFPTX0_P") (class "Default")
      (node (ref "IC27") (pin "R4") (pinfunction "MGTHTXP3_226_R4") (pintype "output"))
    )
    (net (code "91") (name "/QSFPTX1_N") (class "Default")
      (node (ref "IC27") (pin "U3") (pinfunction "MGTHTXN2_226_U3") (pintype "output"))
    )
    (net (code "92") (name "/QSFPTX1_P") (class "Default")
      (node (ref "IC27") (pin "U4") (pinfunction "MGTHTXP2_226_U4") (pintype "output"))
    )
    (net (code "93") (name "/QSFPTX2_N") (class "Default")
      (node (ref "IC27") (pin "W3") (pinfunction "MGTHTXN1_226_W3") (pintype "output"))
    )
    (net (code "94") (name "/QSFPTX2_P") (class "Default")
      (node (ref "IC27") (pin "W4") (pinfunction "MGTHTXP1_226_W4") (pintype "output"))
    )
    (net (code "95") (name "/QSFPTX3_N") (class "Default")
      (node (ref "IC27") (pin "AA3") (pinfunction "MGTHTXN0_226_AA3") (pintype "output"))
    )
    (net (code "96") (name "/QSFPTX3_P") (class "Default")
      (node (ref "IC27") (pin "AA4") (pinfunction "MGTHTXP0_226_AA4") (pintype "output"))
    )
    (net (code "97") (name "/QSFPTX4_N") (class "Default")
      (node (ref "IC27") (pin "B5") (pinfunction "MGTHTXN3_228_B5") (pintype "output"))
    )
    (net (code "98") (name "/QSFPTX4_P") (class "Default")
      (node (ref "IC27") (pin "B6") (pinfunction "MGTHTXP3_228_B6") (pintype "output"))
    )
    (net (code "99") (name "/QSFPTX5_N") (class "Default")
      (node (ref "IC27") (pin "C3") (pinfunction "MGTHTXN2_228_C3") (pintype "output"))
    )
    (net (code "100") (name "/QSFPTX5_P") (class "Default")
      (node (ref "IC27") (pin "C4") (pinfunction "MGTHTXP2_228_C4") (pintype "output"))
    )
    (net (code "101") (name "/QSFPTX6_N") (class "Default")
      (node (ref "IC27") (pin "D5") (pinfunction "MGTHTXN1_228_D5") (pintype "output"))
    )
    (net (code "102") (name "/QSFPTX6_P") (class "Default")
      (node (ref "IC27") (pin "D6") (pinfunction "MGTHTXP1_228_D6") (pintype "output"))
    )
    (net (code "103") (name "/QSFPTX7_N") (class "Default")
      (node (ref "IC27") (pin "F5") (pinfunction "MGTHTXN0_228_F5") (pintype "output"))
    )
    (net (code "104") (name "/QSFPTX7_P") (class "Default")
      (node (ref "IC27") (pin "F6") (pinfunction "MGTHTXP0_228_F6") (pintype "output"))
    )
    (net (code "105") (name "/REFCLK226_UFL_N") (class "Default")
      (node (ref "C712") (pin "1") (pinfunction "1_1") (pintype "passive"))
      (node (ref "IC27") (pin "T5") (pinfunction "MGTREFCLK1N_226_T5") (pintype "input"))
    )
    (net (code "106") (name "/REFCLK226_UFL_P") (class "Default")
      (node (ref "C711") (pin "1") (pinfunction "1_1") (pintype "passive"))
      (node (ref "IC27") (pin "T6") (pinfunction "MGTREFCLK1P_226_T6") (pintype "input"))
    )
    (net (code "107") (name "/REFCLK228_C_N") (class "Default")
      (node (ref "C610") (pin "1") (pinfunction "1_1") (pintype "passive"))
      (node (ref "IC27") (pin "K5") (pinfunction "MGTREFCLK0N_228_K5") (pintype "input"))
    )
    (net (code "108") (name "/REFCLK228_C_P") (class "Default")
      (node (ref "C609") (pin "1") (pinfunction "1_1") (pintype "passive"))
      (node (ref "IC27") (pin "K6") (pinfunction "MGTREFCLK0P_228_K6") (pintype "input"))
    )
    (net (code "109") (name "/REFCLK228_UFL_N") (class "Default")
      (node (ref "C611") (pin "1") (pinfunction "1_1") (pintype "passive"))
      (node (ref "IC27") (pin "H5") (pinfunction "MGTREFCLK1N_228_H5") (pintype "input"))
    )
    (net (code "110") (name "/REFCLK228_UFL_P") (class "Default")
      (node (ref "C612") (pin "1") (pinfunction "1_1") (pintype "passive"))
      (node (ref "IC27") (pin "H6") (pinfunction "MGTREFCLK1P_228_H6") (pintype "input"))
    )
    (net (code "111") (name "/TX0_N") (class "Default")
      (node (ref "C633") (pin "2") (pinfunction "2_2") (pintype "passive"))
      (node (ref "J27") (pin "3") (pinfunction "A-_3") (pintype "bidirectional"))
    )
    (net (code "112") (name "/TX0_P") (class "Default")
      (node (ref "C634") (pin "2") (pinfunction "2_2") (pintype "passive"))
      (node (ref "J27") (pin "2") (pinfunction "A+_2") (pintype "bidirectional"))
    )
    (net (code "113") (name "/TX1_N") (class "Default")
      (node (ref "C635") (pin "2") (pinfunction "2_2") (pintype "passive"))
      (node (ref "J26") (pin "3") (pinfunction "A-_3") (pintype "bidirectional"))
    )
    (net (code "114") (name "/TX1_P") (class "Default")
      (node (ref "C636") (pin "2") (pinfunction "2_2") (pintype "passive"))
      (node (ref "J26") (pin "2") (pinfunction "A+_2") (pintype "bidirectional"))
    )
    (net (code "115") (name "/TX2_N") (class "Default")
      (node (ref "C637") (pin "2") (pinfunction "2_2") (pintype "passive"))
      (node (ref "J25") (pin "3") (pinfunction "A-_3") (pintype "bidirectional"))
    )
    (net (code "116") (name "/TX2_P") (class "Default")
      (node (ref "C638") (pin "2") (pinfunction "2_2") (pintype "passive"))
      (node (ref "J25") (pin "2") (pinfunction "A+_2") (pintype "bidirectional"))
    )
    (net (code "117") (name "/Tx4_N") (class "Default")
      (node (ref "C631") (pin "2") (pinfunction "2_2") (pintype "passive"))
    )
    (net (code "118") (name "/Tx4_P") (class "Default")
      (node (ref "C632") (pin "2") (pinfunction "2_2") (pintype "passive"))
    )
    (net (code "119") (name "/Tx5_N") (class "Default")
      (node (ref "C626") (pin "2") (pinfunction "2_2") (pintype "passive"))
    )
    (net (code "120") (name "/Tx5_P") (class "Default")
      (node (ref "C627") (pin "2") (pinfunction "2_2") (pintype "passive"))
    )
    (net (code "121") (name "/Tx6_N") (class "Default")
      (node (ref "C619") (pin "2") (pinfunction "2_2") (pintype "passive"))
    )
    (net (code "122") (name "/Tx6_P") (class "Default")
      (node (ref "C621") (pin "2") (pinfunction "2_2") (pintype "passive"))
    )
    (net (code "123") (name "/Tx7_N") (class "Default")
      (node (ref "C615") (pin "2") (pinfunction "2_2") (pintype "passive"))
    )
    (net (code "124") (name "/Tx7_P") (class "Default")
      (node (ref "C616") (pin "2") (pinfunction "2_2") (pintype "passive"))
    )
    (net (code "125") (name "/Tx12_N") (class "Default")
      (node (ref "C628") (pin "1") (pinfunction "1_1") (pintype "passive"))
    )
    (net (code "126") (name "/Tx12_P") (class "Default")
      (node (ref "C630") (pin "1") (pinfunction "1_1") (pintype "passive"))
    )
    (net (code "127") (name "/Tx13_N") (class "Default")
      (node (ref "C624") (pin "1") (pinfunction "1_1") (pintype "passive"))
    )
    (net (code "128") (name "/Tx13_P") (class "Default")
      (node (ref "C625") (pin "1") (pinfunction "1_1") (pintype "passive"))
    )
    (net (code "129") (name "/Tx14_N") (class "Default")
      (node (ref "C617") (pin "1") (pinfunction "1_1") (pintype "passive"))
    )
    (net (code "130") (name "/Tx14_P") (class "Default")
      (node (ref "C618") (pin "1") (pinfunction "1_1") (pintype "passive"))
    )
    (net (code "131") (name "/Tx15_N") (class "Default")
      (node (ref "C613") (pin "1") (pinfunction "1_1") (pintype "passive"))
    )
    (net (code "132") (name "/Tx15_P") (class "Default")
      (node (ref "C614") (pin "1") (pinfunction "1_1") (pintype "passive"))
    )
    (net (code "139") (name "GND") (class "Default")
      (node (ref "C623") (pin "1") (pinfunction "1_1") (pintype "passive"))
      (node (ref "C629") (pin "1") (pinfunction "1_1") (pintype "passive"))
      (node (ref "J11") (pin "2") (pinfunction "2_2") (pintype "bidirectional"))
      (node (ref "J12") (pin "2") (pinfunction "2_2") (pintype "bidirectional"))
      (node (ref "J21") (pin "2") (pinfunction "2_2") (pintype "bidirectional"))
      (node (ref "J22") (pin "2") (pinfunction "2_2") (pintype "bidirectional"))
      (node (ref "J23") (pin "2") (pinfunction "2_2") (pintype "bidirectional"))
      (node (ref "J24") (pin "2") (pinfunction "2_2") (pintype "bidirectional"))
      (node (ref "J25") (pin "1") (pinfunction "GND_1") (pintype "power_in"))
      (node (ref "J25") (pin "4") (pinfunction "GND_4") (pintype "power_in"))
      (node (ref "J25") (pin "7") (pinfunction "GND_7") (pintype "power_in"))
      (node (ref "J26") (pin "1") (pinfunction "GND_1") (pintype "power_in"))
      (node (ref "J26") (pin "4") (pinfunction "GND_4") (pintype "power_in"))
      (node (ref "J26") (pin "7") (pinfunction "GND_7") (pintype "power_in"))
      (node (ref "J27") (pin "1") (pinfunction "GND_1") (pintype "power_in"))
      (node (ref "J27") (pin "4") (pinfunction "GND_4") (pintype "power_in"))
      (node (ref "J27") (pin "7") (pinfunction "GND_7") (pintype "power_in"))
      (node (ref "OSC3") (pin "3") (pinfunction "GND_3") (pintype "power_in"))
      (node (ref "OSC4") (pin "3") (pinfunction "GND_3") (pintype "power_in"))
      (node (ref "R414") (pin "2") (pinfunction "2_2") (pintype "passive"))
      (node (ref "R415") (pin "2") (pinfunction "2_2") (pintype "passive"))
      (node (ref "R416") (pin "2") (pinfunction "2_2") (pintype "passive"))
      (node (ref "R417") (pin "2") (pinfunction "2_2") (pintype "passive"))
    )
    (net (code "140") (name "Net-(C609-Pad2)") (class "Default")
      (node (ref "C609") (pin "2") (pinfunction "2_2") (pintype "passive"))
      (node (ref "J21") (pin "1") (pinfunction "1_1") (pintype "bidirectional"))
    )
    (net (code "141") (name "Net-(C610-Pad2)") (class "Default")
      (node (ref "C610") (pin "2") (pinfunction "2_2") (pintype "passive"))
      (node (ref "J22") (pin "1") (pinfunction "1_1") (pintype "bidirectional"))
    )
    (net (code "142") (name "Net-(C611-Pad2)") (class "Default")
      (node (ref "C611") (pin "2") (pinfunction "2_2") (pintype "passive"))
      (node (ref "J23") (pin "1") (pinfunction "1_1") (pintype "bidirectional"))
    )
    (net (code "143") (name "Net-(C612-Pad2)") (class "Default")
      (node (ref "C612") (pin "2") (pinfunction "2_2") (pintype "passive"))
      (node (ref "J24") (pin "1") (pinfunction "1_1") (pintype "bidirectional"))
    )
    (net (code "144") (name "Net-(C620-Pad1)") (class "Default")
      (node (ref "C620") (pin "1") (pinfunction "1_1") (pintype "passive"))
      (node (ref "R472") (pin "2") (pinfunction "2_2") (pintype "passive"))
    )
    (net (code "145") (name "Net-(C622-Pad1)") (class "Default")
      (node (ref "C622") (pin "1") (pinfunction "1_1") (pintype "passive"))
      (node (ref "R473") (pin "2") (pinfunction "2_2") (pintype "passive"))
    )
    (net (code "146") (name "Net-(C711-Pad2)") (class "Default")
      (node (ref "C711") (pin "2") (pinfunction "2_2") (pintype "passive"))
      (node (ref "J11") (pin "1") (pinfunction "1_1") (pintype "bidirectional"))
    )
    (net (code "147") (name "Net-(C712-Pad2)") (class "Default")
      (node (ref "C712") (pin "2") (pinfunction "2_2") (pintype "passive"))
      (node (ref "J12") (pin "1") (pinfunction "1_1") (pintype "bidirectional"))
    )
    (net (code "148") (name "Net-(OSC3-CLK+)") (class "Default")
      (node (ref "OSC3") (pin "4") (pinfunction "CLK+_4") (pintype "output"))
      (node (ref "R414") (pin "1") (pinfunction "1_1") (pintype "passive"))
      (node (ref "R472") (pin "1") (pinfunction "1_1") (pintype "passive"))
    )
    (net (code "149") (name "Net-(OSC3-CLK-)") (class "Default")
      (node (ref "OSC3") (pin "5") (pinfunction "CLK-_5") (pintype "output"))
      (node (ref "R415") (pin "1") (pinfunction "1_1") (pintype "passive"))
      (node (ref "R473") (pin "1") (pinfunction "1_1") (pintype "passive"))
    )
    (net (code "150") (name "Net-(OSC4-CLK+)") (class "Default")
      (node (ref "OSC4") (pin "4") (pinfunction "CLK+_4") (pintype "output"))
      (node (ref "R416") (pin "1") (pinfunction "1_1") (pintype "passive"))
      (node (ref "R474") (pin "1") (pinfunction "1_1") (pintype "passive"))
    )
    (net (code "151") (name "Net-(OSC4-CLK-)") (class "Default")
      (node (ref "OSC4") (pin "5") (pinfunction "CLK-_5") (pintype "output"))
      (node (ref "R417") (pin "1") (pinfunction "1_1") (pintype "passive"))
      (node (ref "R514") (pin "1") (pinfunction "1_1") (pintype "passive"))
    )
    (net (code "152") (name "P3V3") (class "Default")
      (node (ref "L45") (pin "2") (pinfunction "2_2") (pintype "passive"))
      (node (ref "L46") (pin "2") (pinfunction "2_2") (pintype "passive"))
    )
    (net (code "153") (name "unconnected-(IC27M-MGTREFCLK0N_226-PadV5)") (class "Default")
      (node (ref "IC27") (pin "V5") (pinfunction "MGTREFCLK0N_226_V5") (pintype "input+no_connect"))
    )
    (net (code "154") (name "unconnected-(IC27M-MGTREFCLK0P_226-PadV6)") (class "Default")
      (node (ref "IC27") (pin "V6") (pinfunction "MGTREFCLK0P_226_V6") (pintype "input+no_connect"))
    )
    (net (code "155") (name "unconnected-(OSC3-NC-Pad1)") (class "Default")
      (node (ref "OSC3") (pin "1") (pinfunction "NC_1") (pintype "passive+no_connect"))
    )
    (net (code "156") (name "unconnected-(OSC4-NC-Pad1)") (class "Default")
      (node (ref "OSC4") (pin "1") (pinfunction "NC_1") (pintype "passive+no_connect"))
    )
  )
)
